# AIRDCR.net
KiCad netlist of a schematic drawn in EAGLE
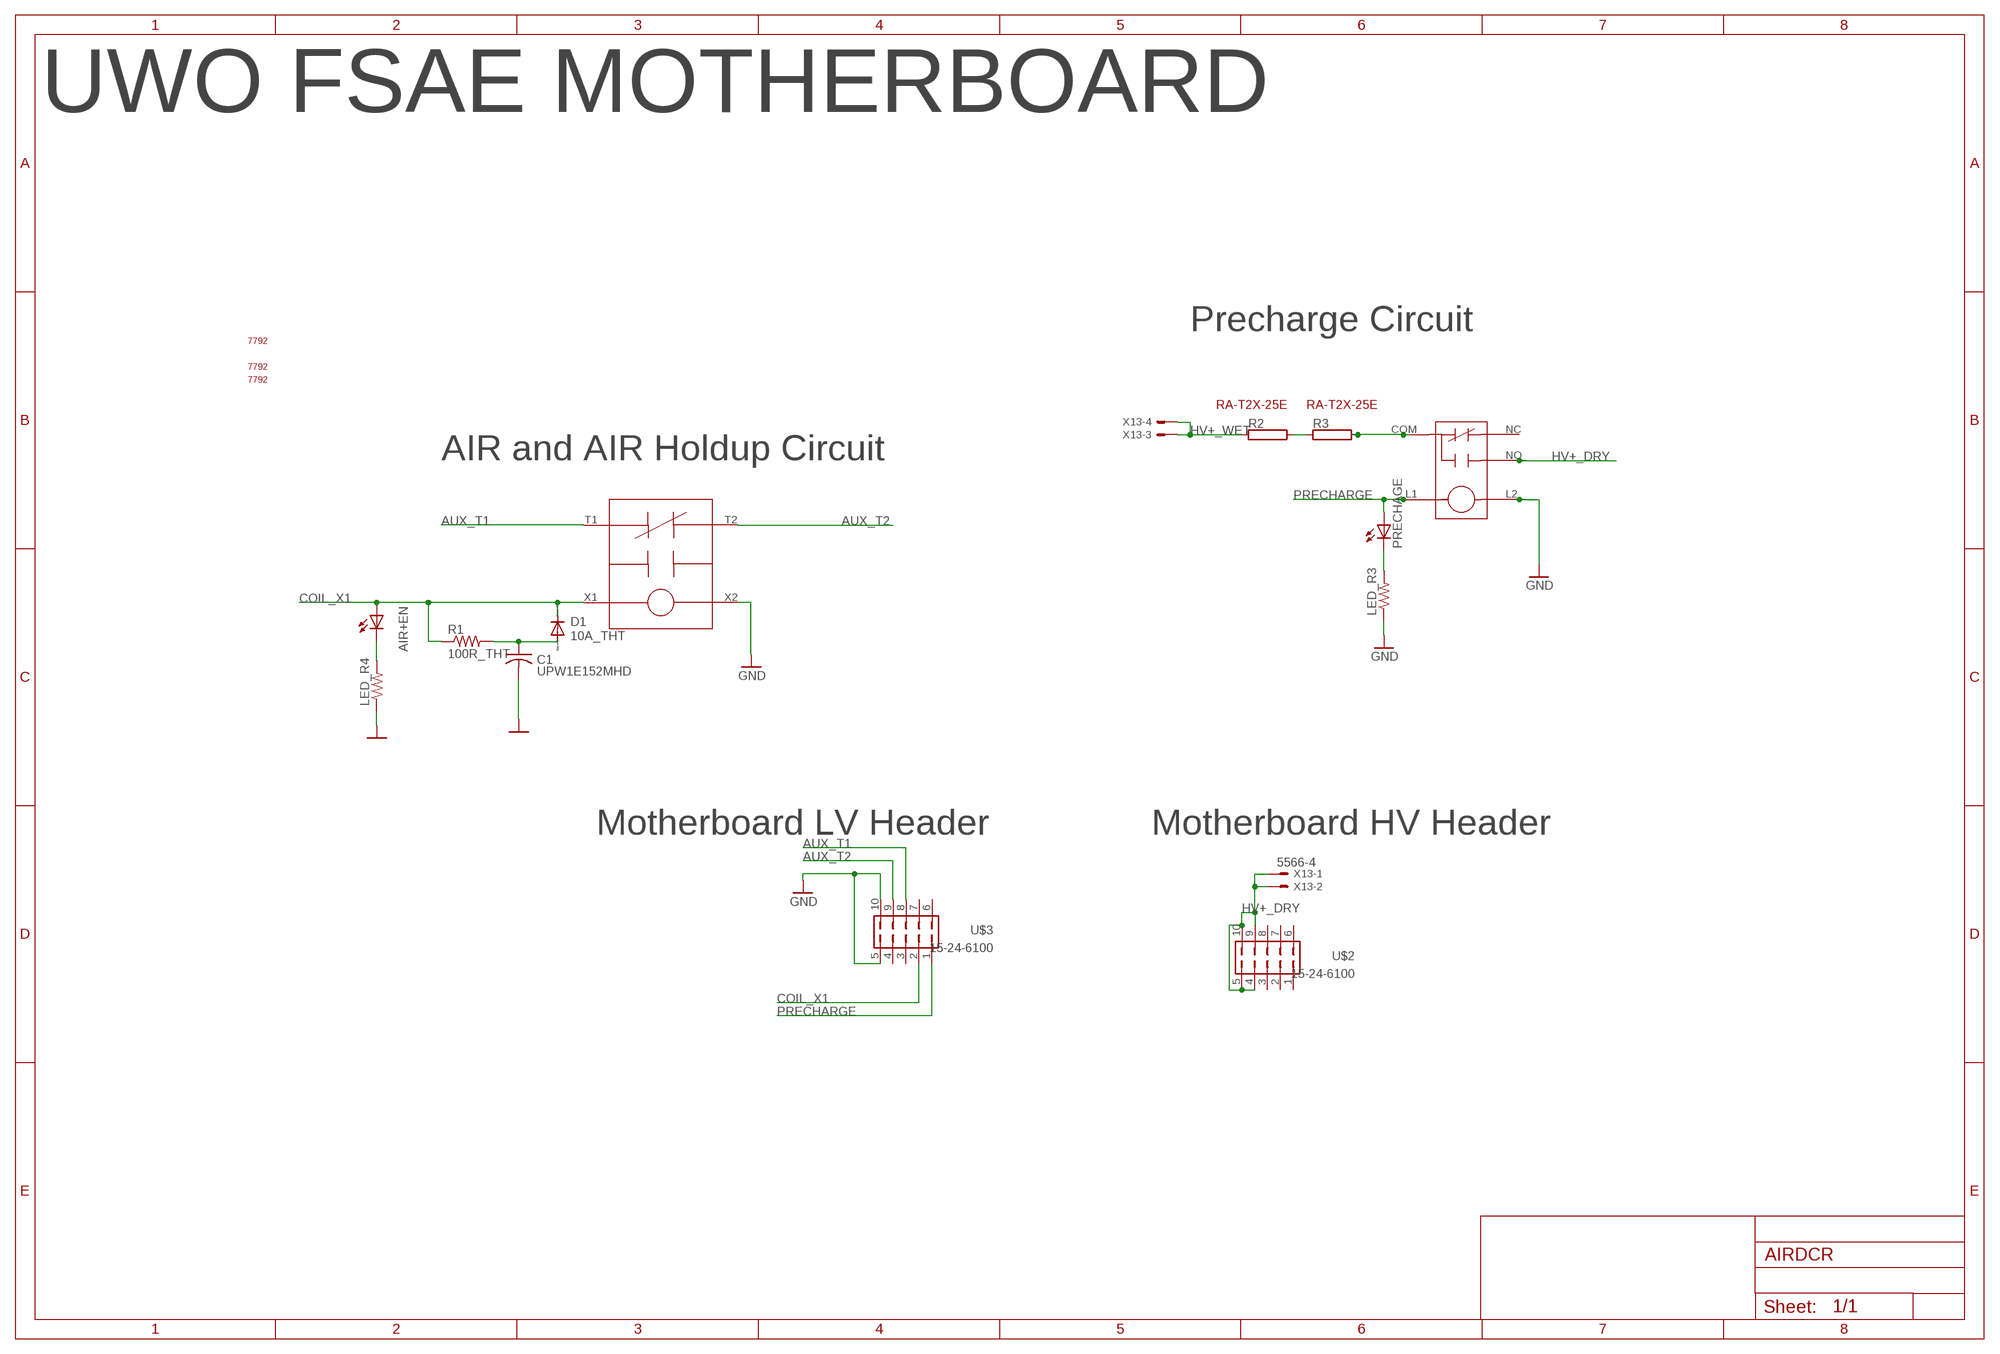
[diagram p0: schematic, sheet 1]

(export (version "E")
  (design (tool "Eeschema 10.0.6"))
  (components
    (comp (ref "AIR+EN")
      (value "LEDCHIPLED_0805")
      (footprint "eagle-import:CHIPLED_0805")
      (libsource (lib "eagle-import") (part "LEDCHIPLED_0805"))
    )
    (comp (ref "C1")
      (value "UPW1E152MHD")
      (footprint "eagle-import:CAPPRD750W65D1800H3700B")
      (libsource (lib "eagle-import") (part "AIR_HOLDUP_CAP"))
    )
    (comp (ref "D1")
      (value "10A_THT")
      (footprint "eagle-import:DIOAD1570W120L850D500B")
      (libsource (lib "eagle-import") (part "AIR_HOLDUP_DIODE"))
    )
    (comp (ref "LED_R3")
      (value "R-US_R0805")
      (footprint "eagle-import:R0805")
      (libsource (lib "eagle-import") (part "R-US_R0805"))
    )
    (comp (ref "LED_R4")
      (value "R-US_R0805")
      (footprint "eagle-import:R0805")
      (libsource (lib "eagle-import") (part "R-US_R0805"))
    )
    (comp (ref "PRECHAGE")
      (value "LEDCHIPLED_0805")
      (footprint "eagle-import:CHIPLED_0805")
      (libsource (lib "eagle-import") (part "LEDCHIPLED_0805"))
    )
    (comp (ref "R1")
      (value "100R_THT")
      (footprint "eagle-import:RESAD976W63L650D250B")
      (libsource (lib "eagle-import") (part "AIR_HOLDUP_RESISTOR"))
    )
    (comp (ref "R2")
      (value "RMG100-V")
      (footprint "eagle-import:TO-247-2V")
      (libsource (lib "eagle-import") (part "RMG100-V"))
    )
    (comp (ref "R3")
      (value "RMG100-V")
      (footprint "eagle-import:TO-247-2V")
      (libsource (lib "eagle-import") (part "RMG100-V"))
    )
    (comp (ref "U$1")
      (value "GV245BPB")
      (footprint "eagle-import:GV224")
      (libsource (lib "eagle-import") (part "GV224"))
    )
    (comp (ref "U$2")
      (value "15-24-6100")
      (footprint "eagle-import:15-24-6100")
      (libsource (lib "eagle-import") (part "15-24-6100"))
    )
    (comp (ref "U$3")
      (value "15-24-6100")
      (footprint "eagle-import:15-24-6100")
      (libsource (lib "eagle-import") (part "15-24-6100"))
    )
    (comp (ref "U$4")
      (value "G81C335")
      (footprint "eagle-import:G81C335")
      (libsource (lib "eagle-import") (part "G81C335"))
    )
    (comp (ref "U$5")
      (value "7792")
      (footprint "eagle-import:7792")
      (libsource (lib "eagle-import") (part "7792"))
    )
    (comp (ref "U$6")
      (value "7792")
      (footprint "eagle-import:7792")
      (libsource (lib "eagle-import") (part "7792"))
    )
    (comp (ref "U$7")
      (value "7792")
      (footprint "eagle-import:7792")
      (libsource (lib "eagle-import") (part "7792"))
    )
    (comp (ref "U$8")
      (value "RA-T2X-25E")
      (footprint "eagle-import:RA-T2X-25E")
      (libsource (lib "eagle-import") (part "RA-T2X-25E"))
    )
    (comp (ref "U$9")
      (value "RA-T2X-25E")
      (footprint "eagle-import:RA-T2X-25E")
      (libsource (lib "eagle-import") (part "RA-T2X-25E"))
    )
    (comp (ref "X13")
      (value "5566-4")
      (footprint "eagle-import:5566-4")
      (fields (field (name "MF") "MOLEX"))
      (libsource (lib "eagle-import") (part "5566-4"))
    )
  )
  (nets
    (net (code "1") (name "/AUX_T1") (class "Default")
      (node (ref "U$1") (pin "T1") (pinfunction "T1_T1") (pintype "bidirectional"))
      (node (ref "U$3") (pin "8") (pinfunction "8_8") (pintype "passive"))
    )
    (net (code "2") (name "/AUX_T2") (class "Default")
      (node (ref "U$1") (pin "T2") (pinfunction "T2_T2") (pintype "bidirectional"))
      (node (ref "U$3") (pin "9") (pinfunction "9_9") (pintype "passive"))
    )
    (net (code "3") (name "/COIL_X1") (class "Default")
      (node (ref "AIR+EN") (pin "A") (pinfunction "A_A") (pintype "passive"))
      (node (ref "D1") (pin "1") (pinfunction "C_1") (pintype "passive"))
      (node (ref "R1") (pin "1") (pinfunction "1_1") (pintype "passive"))
      (node (ref "U$1") (pin "X1") (pinfunction "X1_X1") (pintype "bidirectional"))
      (node (ref "U$3") (pin "2") (pinfunction "2_2") (pintype "passive"))
    )
    (net (code "4") (name "/HV+_DRY") (class "Default")
      (node (ref "U$2") (pin "10") (pinfunction "10_10") (pintype "passive"))
      (node (ref "U$2") (pin "4") (pinfunction "4_4") (pintype "passive"))
      (node (ref "U$2") (pin "5") (pinfunction "5_5") (pintype "passive"))
      (node (ref "U$2") (pin "9") (pinfunction "9_9") (pintype "passive"))
      (node (ref "U$4") (pin "NO") (pinfunction "NO_NO") (pintype "bidirectional"))
      (node (ref "X13") (pin "1") (pinfunction "S_1") (pintype "passive"))
      (node (ref "X13") (pin "2") (pinfunction "S_2") (pintype "passive"))
    )
    (net (code "5") (name "/HV+_WET") (class "Default")
      (node (ref "R2") (pin "1") (pinfunction "1_1") (pintype "passive"))
      (node (ref "X13") (pin "3") (pinfunction "S_3") (pintype "passive"))
      (node (ref "X13") (pin "4") (pinfunction "S_4") (pintype "passive"))
    )
    (net (code "6") (name "/PRECHARGE") (class "Default")
      (node (ref "PRECHAGE") (pin "A") (pinfunction "A_A") (pintype "passive"))
      (node (ref "U$3") (pin "1") (pinfunction "1_1") (pintype "passive"))
      (node (ref "U$4") (pin "L1") (pinfunction "L1_L1") (pintype "bidirectional"))
    )
    (net (code "7") (name "GND") (class "Default")
      (node (ref "C1") (pin "2") (pinfunction "2_2") (pintype "passive"))
      (node (ref "LED_R3") (pin "1") (pinfunction "1_1") (pintype "passive"))
      (node (ref "LED_R4") (pin "1") (pinfunction "1_1") (pintype "passive"))
      (node (ref "U$1") (pin "X2") (pinfunction "X2_X2") (pintype "bidirectional"))
      (node (ref "U$3") (pin "10") (pinfunction "10_10") (pintype "passive"))
      (node (ref "U$3") (pin "5") (pinfunction "5_5") (pintype "passive"))
      (node (ref "U$4") (pin "L2") (pinfunction "L2_L2") (pintype "bidirectional"))
    )
    (net (code "8") (name "Net-(AIR+EN-PadC)") (class "Default")
      (node (ref "AIR+EN") (pin "C") (pinfunction "C_C") (pintype "passive"))
      (node (ref "LED_R4") (pin "2") (pinfunction "2_2") (pintype "passive"))
    )
    (net (code "9") (name "Net-(D1-A)") (class "Default")
      (node (ref "C1") (pin "1") (pinfunction "1_1") (pintype "passive"))
      (node (ref "D1") (pin "2") (pinfunction "A_2") (pintype "passive"))
      (node (ref "R1") (pin "2") (pinfunction "2_2") (pintype "passive"))
    )
    (net (code "10") (name "Net-(LED_R3-Pad2)") (class "Default")
      (node (ref "LED_R3") (pin "2") (pinfunction "2_2") (pintype "passive"))
      (node (ref "PRECHAGE") (pin "C") (pinfunction "C_C") (pintype "passive"))
    )
    (net (code "11") (name "Net-(R2-Pad2)") (class "Default")
      (node (ref "R2") (pin "2") (pinfunction "2_2") (pintype "passive"))
      (node (ref "R3") (pin "1") (pinfunction "1_1") (pintype "passive"))
    )
    (net (code "12") (name "Net-(R3-Pad2)") (class "Default")
      (node (ref "R3") (pin "2") (pinfunction "2_2") (pintype "passive"))
      (node (ref "U$4") (pin "COM") (pinfunction "COM_COM") (pintype "bidirectional"))
    )
    (net (code "13") (name "unconnected-(U$2-Pad1)") (class "Default")
      (node (ref "U$2") (pin "1") (pinfunction "1_1") (pintype "passive"))
    )
    (net (code "14") (name "unconnected-(U$2-Pad2)") (class "Default")
      (node (ref "U$2") (pin "2") (pinfunction "2_2") (pintype "passive"))
    )
    (net (code "15") (name "unconnected-(U$2-Pad3)") (class "Default")
      (node (ref "U$2") (pin "3") (pinfunction "3_3") (pintype "passive"))
    )
    (net (code "16") (name "unconnected-(U$2-Pad6)") (class "Default")
      (node (ref "U$2") (pin "6") (pinfunction "6_6") (pintype "passive"))
    )
    (net (code "17") (name "unconnected-(U$2-Pad7)") (class "Default")
      (node (ref "U$2") (pin "7") (pinfunction "7_7") (pintype "passive"))
    )
    (net (code "18") (name "unconnected-(U$2-Pad8)") (class "Default")
      (node (ref "U$2") (pin "8") (pinfunction "8_8") (pintype "passive"))
    )
    (net (code "19") (name "unconnected-(U$3-Pad3)") (class "Default")
      (node (ref "U$3") (pin "3") (pinfunction "3_3") (pintype "passive"))
    )
    (net (code "20") (name "unconnected-(U$3-Pad4)") (class "Default")
      (node (ref "U$3") (pin "4") (pinfunction "4_4") (pintype "passive"))
    )
    (net (code "21") (name "unconnected-(U$3-Pad6)") (class "Default")
      (node (ref "U$3") (pin "6") (pinfunction "6_6") (pintype "passive"))
    )
    (net (code "22") (name "unconnected-(U$3-Pad7)") (class "Default")
      (node (ref "U$3") (pin "7") (pinfunction "7_7") (pintype "passive"))
    )
    (net (code "23") (name "unconnected-(U$4-PadNC)") (class "Default")
      (node (ref "U$4") (pin "NC") (pinfunction "NC_NC") (pintype "bidirectional"))
    )
  )
)
